# 08-STM32-01.net
KiCad netlist of a schematic drawn in Altium Designer
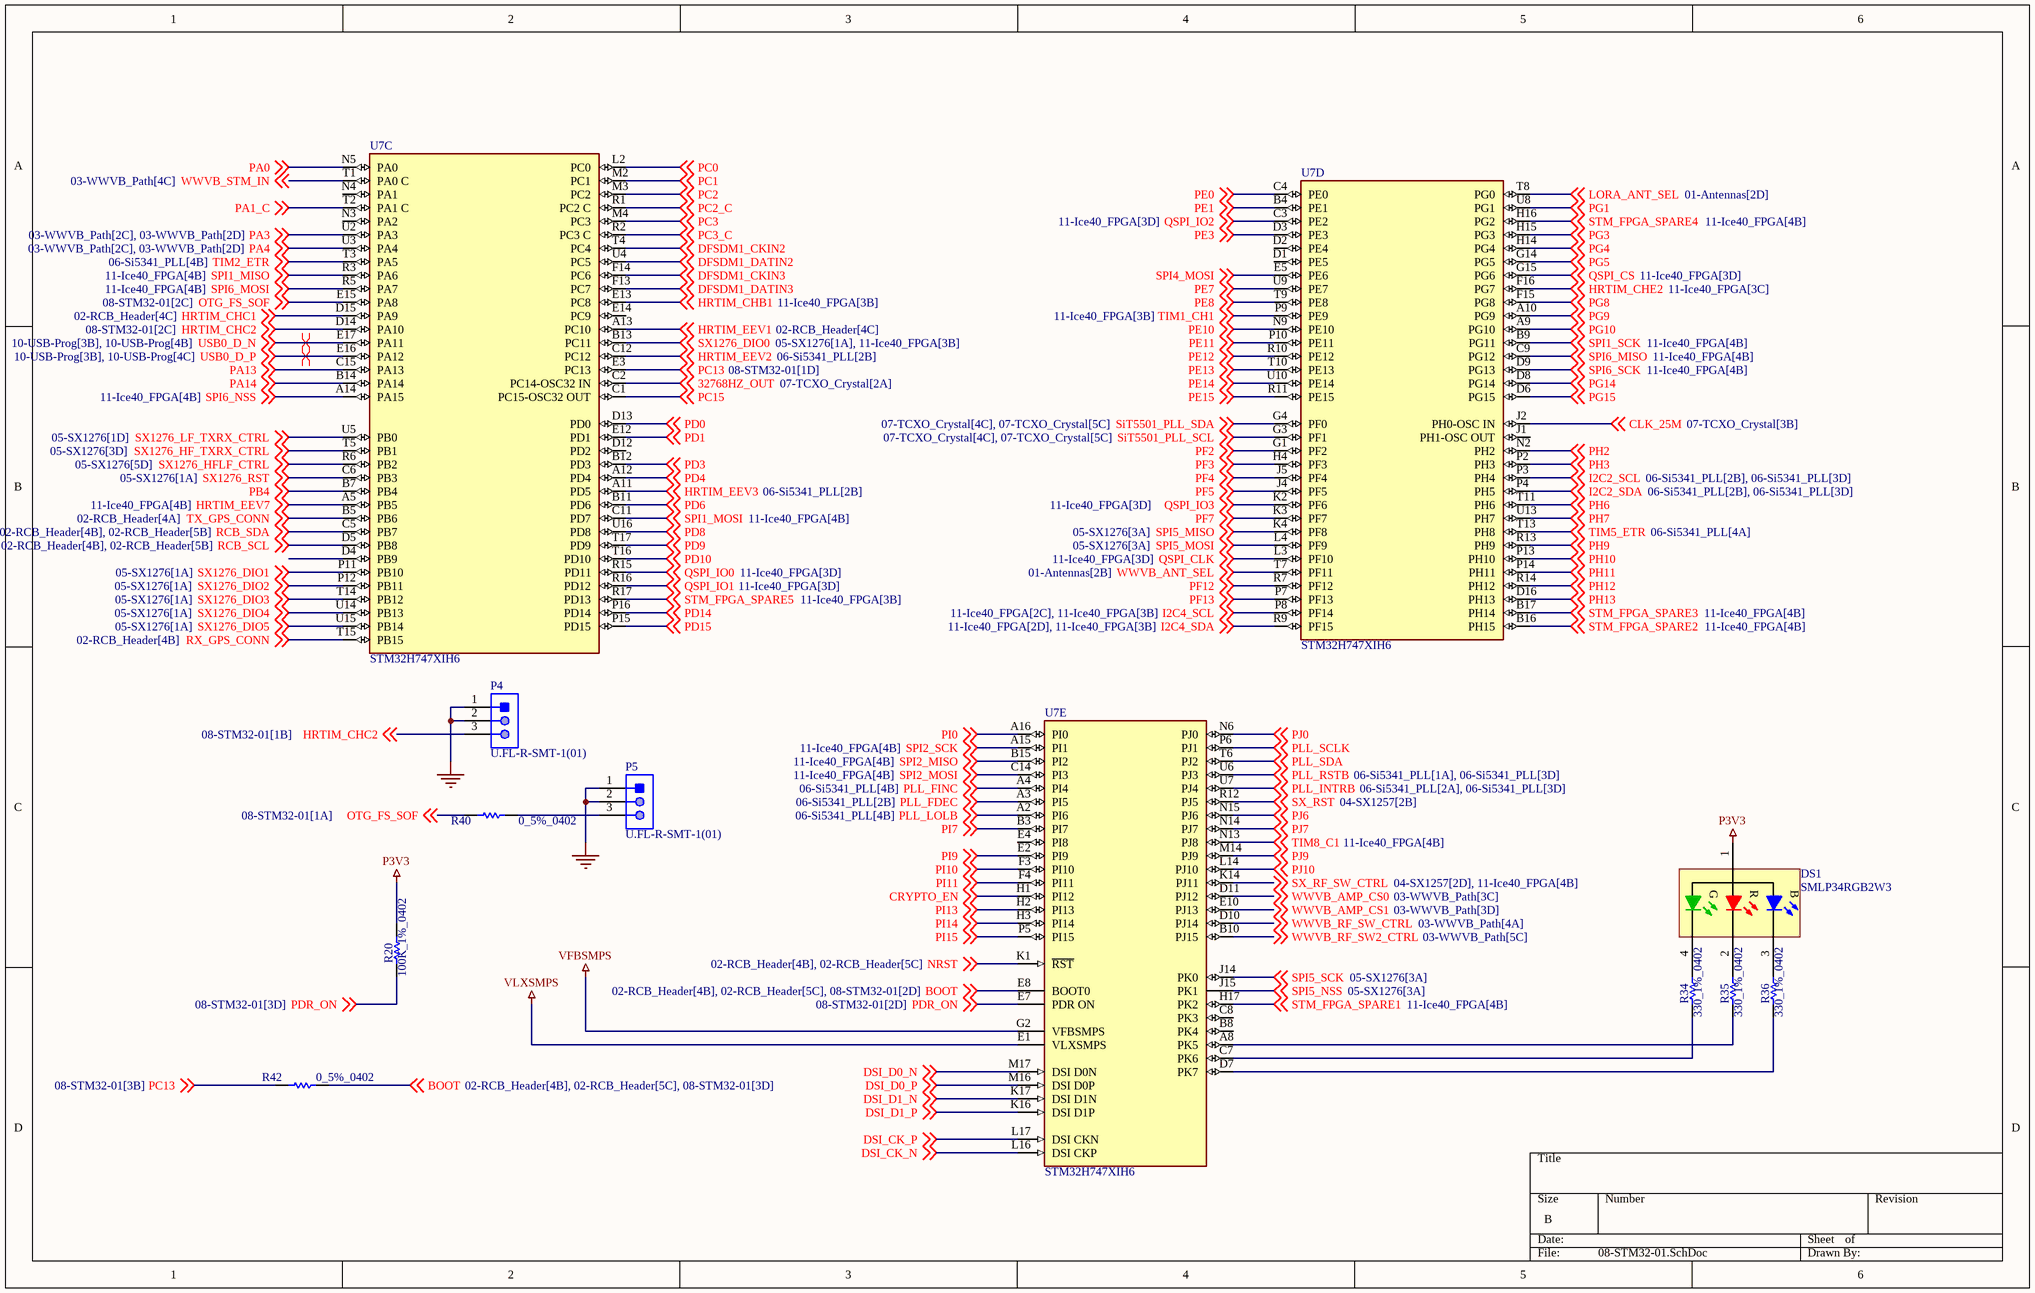
[diagram p0: 08-STM32-01.SchDoc]

(export (version "E")
  (design (tool "Eeschema 10.0.6"))
  (components
    (comp (ref "DS1")
      (value "SMLP34RGB2W3")
      (footprint "ROHM-SMLP34-4_V")
      (description "PICOLED-RGB LED, 5 mA, -40 to 85 degC, 4-Pin 1 x 1 x 0.25 mm SMD, RoHS, Tape and Reel")
      (fields (field (name "MANUFACTURER") "ROHM Semiconductor"))
      (libsource (lib "Altium Content Vault") (part "ROHM-LED_RGB_A1R2B3G4-4"))
    )
    (comp (ref "P4")
      (value "U.FL-R-SMT-1(01)")
      (footprint "HRS-U.FL-R-SMT-3_V")
      (description "Ultra Small Coaxial Connector, 6 GHz, -40 to 90 degC, 3-Pin SMD, RoHS, Bulk")
      (fields (field (name "MANUFACTURER") "Hirose Electric"))
      (libsource (lib "Altium Content Vault") (part "CN-1P-M-R3"))
    )
    (comp (ref "P5")
      (value "U.FL-R-SMT-1(01)")
      (footprint "HRS-U.FL-R-SMT-3_V")
      (description "Ultra Small Coaxial Connector, 6 GHz, -40 to 90 degC, 3-Pin SMD, RoHS, Bulk")
      (fields (field (name "MANUFACTURER") "Hirose Electric"))
      (libsource (lib "Altium Content Vault") (part "CN-1P-M-R3"))
    )
    (comp (ref "R20")
      (value "100K_1%_0402")
      (footprint "RESC1005X40X25ML05T10")
      (fields (field (name "MANUFACTURER") "Yageo") (field (name "PART NUMBER") "RC0402FR-13100KL"))
      (libsource (lib "Altium Content Vault") (part "RES"))
    )
    (comp (ref "R34")
      (value "330_1%_0402")
      (footprint "RESC1005X40X25NL10T10")
      (fields (field (name "MANUFACTURER") "Panasonic") (field (name "PART NUMBER") "ERA-2AED331X"))
      (libsource (lib "Altium Content Vault") (part "RES"))
    )
    (comp (ref "R35")
      (value "330_1%_0402")
      (footprint "RESC1005X40X25NL10T10")
      (fields (field (name "MANUFACTURER") "Panasonic") (field (name "PART NUMBER") "ERA-2AED331X"))
      (libsource (lib "Altium Content Vault") (part "RES"))
    )
    (comp (ref "R36")
      (value "330_1%_0402")
      (footprint "RESC1005X40X25NL10T10")
      (fields (field (name "MANUFACTURER") "Panasonic") (field (name "PART NUMBER") "ERA-2AED331X"))
      (libsource (lib "Altium Content Vault") (part "RES"))
    )
    (comp (ref "R40")
      (value "0_5%_0402")
      (footprint "RESC1005X40X25NL05T10")
      (fields (field (name "MANUFACTURER") "Panasonic") (field (name "PART NUMBER") "ERJ-U020R00X"))
      (libsource (lib "Altium Content Vault") (part "RES"))
    )
    (comp (ref "R42")
      (value "0_5%_0402")
      (footprint "RESC1005X40X25NL05T10")
      (fields (field (name "MANUFACTURER") "Panasonic") (field (name "PART NUMBER") "ERJ-U020R00X"))
      (libsource (lib "Altium Content Vault") (part "RES"))
    )
    (comp (ref "U7")
      (value "STM32H747XIH6")
      (footprint "FP-TFBGA240+25-A07U-MFG")
      (description "HIGH-PERFORMANCE AND DSP WITH DP")
      (fields
        (field (name "MANUFACTURER") "STMicroelectronics")
        (field (name "OCTOPART") "https://octopart.com/stm32h747xih6-stmicroelectronics-100293943")
      )
      (libsource (lib "Altium Content Vault") (part "41f839bdfd00d9510c8672f0f410bfb"))
    )
  )
  (nets
    (net (code "1") (name "32768HZ_OUT") (class "Default")
      (node (ref "U7") (pin "C2") (pinfunction "PC14-OSC32_IN_C2") (pintype "bidirectional"))
    )
    (net (code "2") (name "BOOT") (class "Default")
      (node (ref "R42") (pin "2") (pinfunction "2_2") (pintype "passive"))
      (node (ref "U7") (pin "E8") (pinfunction "BOOT0_E8") (pintype "passive"))
    )
    (net (code "3") (name "CLK_25M") (class "Default")
      (node (ref "U7") (pin "J2") (pinfunction "PH0-OSC_IN_J2") (pintype "bidirectional"))
    )
    (net (code "4") (name "CRYPTO_EN") (class "Default")
      (node (ref "U7") (pin "H1") (pinfunction "PI12_H1") (pintype "bidirectional"))
    )
    (net (code "5") (name "DFSDM1_CKIN2") (class "Default")
      (node (ref "U7") (pin "T4") (pinfunction "PC4_T4") (pintype "bidirectional"))
    )
    (net (code "6") (name "DFSDM1_CKIN3") (class "Default")
      (node (ref "U7") (pin "F14") (pinfunction "PC6_F14") (pintype "bidirectional"))
    )
    (net (code "7") (name "DFSDM1_DATIN2") (class "Default")
      (node (ref "U7") (pin "U4") (pinfunction "PC5_U4") (pintype "bidirectional"))
    )
    (net (code "8") (name "DFSDM1_DATIN3") (class "Default")
      (node (ref "U7") (pin "F13") (pinfunction "PC7_F13") (pintype "bidirectional"))
    )
    (net (code "9") (name "DSI_CK_N") (class "Default")
      (node (ref "U7") (pin "L16") (pinfunction "DSI_CKP_L16") (pintype "input"))
    )
    (net (code "10") (name "DSI_CK_P") (class "Default")
      (node (ref "U7") (pin "L17") (pinfunction "DSI_CKN_L17") (pintype "input"))
    )
    (net (code "11") (name "DSI_D0_N") (class "Default")
      (node (ref "U7") (pin "M17") (pinfunction "DSI_D0N_M17") (pintype "input"))
    )
    (net (code "12") (name "DSI_D0_P") (class "Default")
      (node (ref "U7") (pin "M16") (pinfunction "DSI_D0P_M16") (pintype "input"))
    )
    (net (code "13") (name "DSI_D1_N") (class "Default")
      (node (ref "U7") (pin "K17") (pinfunction "DSI_D1N_K17") (pintype "input"))
    )
    (net (code "14") (name "DSI_D1_P") (class "Default")
      (node (ref "U7") (pin "K16") (pinfunction "DSI_D1P_K16") (pintype "input"))
    )
    (net (code "15") (name "GND") (class "Default")
      (node (ref "P4") (pin "1") (pinfunction "1_1") (pintype "passive"))
      (node (ref "P4") (pin "2") (pinfunction "2_2") (pintype "passive"))
      (node (ref "P5") (pin "1") (pinfunction "1_1") (pintype "passive"))
      (node (ref "P5") (pin "2") (pinfunction "2_2") (pintype "passive"))
    )
    (net (code "16") (name "HRTIM_CHB1") (class "Default")
      (node (ref "U7") (pin "E13") (pinfunction "PC8_E13") (pintype "bidirectional"))
    )
    (net (code "17") (name "HRTIM_CHC1") (class "Default")
      (node (ref "U7") (pin "D15") (pinfunction "PA9_D15") (pintype "bidirectional"))
    )
    (net (code "18") (name "HRTIM_CHC2") (class "Default")
      (node (ref "P4") (pin "3") (pinfunction "3_3") (pintype "passive"))
      (node (ref "U7") (pin "D14") (pinfunction "PA10_D14") (pintype "bidirectional"))
    )
    (net (code "19") (name "HRTIM_CHE2") (class "Default")
      (node (ref "U7") (pin "F16") (pinfunction "PG7_F16") (pintype "bidirectional"))
    )
    (net (code "20") (name "HRTIM_EEV1") (class "Default")
      (node (ref "U7") (pin "A13") (pinfunction "PC10_A13") (pintype "bidirectional"))
    )
    (net (code "21") (name "HRTIM_EEV2") (class "Default")
      (node (ref "U7") (pin "C12") (pinfunction "PC12_C12") (pintype "bidirectional"))
    )
    (net (code "22") (name "HRTIM_EEV3") (class "Default")
      (node (ref "U7") (pin "A11") (pinfunction "PD5_A11") (pintype "bidirectional"))
    )
    (net (code "23") (name "HRTIM_EEV7") (class "Default")
      (node (ref "U7") (pin "A5") (pinfunction "PB5_A5") (pintype "bidirectional"))
    )
    (net (code "24") (name "I2C2_SCL") (class "Default")
      (node (ref "U7") (pin "P3") (pinfunction "PH4_P3") (pintype "bidirectional"))
    )
    (net (code "25") (name "I2C2_SDA") (class "Default")
      (node (ref "U7") (pin "P4") (pinfunction "PH5_P4") (pintype "bidirectional"))
    )
    (net (code "26") (name "I2C4_SCL") (class "Default")
      (node (ref "U7") (pin "P8") (pinfunction "PF14_P8") (pintype "bidirectional"))
    )
    (net (code "27") (name "I2C4_SDA") (class "Default")
      (node (ref "U7") (pin "R9") (pinfunction "PF15_R9") (pintype "bidirectional"))
    )
    (net (code "28") (name "LORA_ANT_SEL") (class "Default")
      (node (ref "U7") (pin "T8") (pinfunction "PG0_T8") (pintype "bidirectional"))
    )
    (net (code "29") (name "NRST") (class "Default")
      (node (ref "U7") (pin "K1") (pinfunction "~{RST}_K1") (pintype "input"))
    )
    (net (code "30") (name "Net-(DS1-B)") (class "Default")
      (node (ref "DS1") (pin "3") (pinfunction "B_3") (pintype "passive"))
      (node (ref "R36") (pin "2") (pinfunction "2_2") (pintype "passive"))
    )
    (net (code "31") (name "Net-(DS1-G)") (class "Default")
      (node (ref "DS1") (pin "4") (pinfunction "G_4") (pintype "passive"))
      (node (ref "R34") (pin "2") (pinfunction "2_2") (pintype "passive"))
    )
    (net (code "32") (name "Net-(DS1-R)") (class "Default")
      (node (ref "DS1") (pin "2") (pinfunction "R_2") (pintype "passive"))
      (node (ref "R35") (pin "2") (pinfunction "2_2") (pintype "passive"))
    )
    (net (code "33") (name "Net-(P5-Pad3)") (class "Default")
      (node (ref "P5") (pin "3") (pinfunction "3_3") (pintype "passive"))
      (node (ref "R40") (pin "2") (pinfunction "2_2") (pintype "passive"))
    )
    (net (code "34") (name "Net-(U7E-PK5)") (class "Default")
      (node (ref "R35") (pin "1") (pinfunction "1_1") (pintype "passive"))
      (node (ref "U7") (pin "A8") (pinfunction "PK5_A8") (pintype "bidirectional"))
    )
    (net (code "35") (name "Net-(U7E-PK6)") (class "Default")
      (node (ref "R34") (pin "1") (pinfunction "1_1") (pintype "passive"))
      (node (ref "U7") (pin "C7") (pinfunction "PK6_C7") (pintype "bidirectional"))
    )
    (net (code "36") (name "Net-(U7E-PK7)") (class "Default")
      (node (ref "R36") (pin "1") (pinfunction "1_1") (pintype "passive"))
      (node (ref "U7") (pin "D7") (pinfunction "PK7_D7") (pintype "bidirectional"))
    )
    (net (code "37") (name "OTG_FS_SOF") (class "Default")
      (node (ref "R40") (pin "1") (pinfunction "1_1") (pintype "passive"))
      (node (ref "U7") (pin "E15") (pinfunction "PA8_E15") (pintype "bidirectional"))
    )
    (net (code "38") (name "P3V3") (class "Default")
      (node (ref "DS1") (pin "1") (pinfunction "A_1") (pintype "passive"))
      (node (ref "R20") (pin "2") (pinfunction "2_2") (pintype "passive"))
    )
    (net (code "39") (name "PA0") (class "Default")
      (node (ref "U7") (pin "N5") (pinfunction "PA0_N5") (pintype "bidirectional"))
    )
    (net (code "40") (name "PA1_C") (class "Default")
      (node (ref "U7") (pin "T2") (pinfunction "PA1_C_T2") (pintype "bidirectional"))
    )
    (net (code "41") (name "PA3") (class "Default")
      (node (ref "U7") (pin "U2") (pinfunction "PA3_U2") (pintype "bidirectional"))
    )
    (net (code "42") (name "PA4") (class "Default")
      (node (ref "U7") (pin "U3") (pinfunction "PA4_U3") (pintype "bidirectional"))
    )
    (net (code "43") (name "PA13") (class "Default")
      (node (ref "U7") (pin "C15") (pinfunction "PA13_C15") (pintype "bidirectional"))
    )
    (net (code "44") (name "PA14") (class "Default")
      (node (ref "U7") (pin "B14") (pinfunction "PA14_B14") (pintype "bidirectional"))
    )
    (net (code "45") (name "PB4") (class "Default")
      (node (ref "U7") (pin "B7") (pinfunction "PB4_B7") (pintype "bidirectional"))
    )
    (net (code "46") (name "PC0") (class "Default")
      (node (ref "U7") (pin "L2") (pinfunction "PC0_L2") (pintype "bidirectional"))
    )
    (net (code "47") (name "PC1") (class "Default")
      (node (ref "U7") (pin "M2") (pinfunction "PC1_M2") (pintype "bidirectional"))
    )
    (net (code "48") (name "PC2") (class "Default")
      (node (ref "U7") (pin "M3") (pinfunction "PC2_M3") (pintype "bidirectional"))
    )
    (net (code "49") (name "PC2_C") (class "Default")
      (node (ref "U7") (pin "R1") (pinfunction "PC2_C_R1") (pintype "bidirectional"))
    )
    (net (code "50") (name "PC3") (class "Default")
      (node (ref "U7") (pin "M4") (pinfunction "PC3_M4") (pintype "bidirectional"))
    )
    (net (code "51") (name "PC3_C") (class "Default")
      (node (ref "U7") (pin "R2") (pinfunction "PC3_C_R2") (pintype "bidirectional"))
    )
    (net (code "52") (name "PC13") (class "Default")
      (node (ref "R42") (pin "1") (pinfunction "1_1") (pintype "passive"))
      (node (ref "U7") (pin "E3") (pinfunction "PC13_E3") (pintype "bidirectional"))
    )
    (net (code "53") (name "PC15") (class "Default")
      (node (ref "U7") (pin "C1") (pinfunction "PC15-OSC32_OUT_C1") (pintype "bidirectional"))
    )
    (net (code "54") (name "PD0") (class "Default")
      (node (ref "U7") (pin "D13") (pinfunction "PD0_D13") (pintype "bidirectional"))
    )
    (net (code "55") (name "PD1") (class "Default")
      (node (ref "U7") (pin "E12") (pinfunction "PD1_E12") (pintype "bidirectional"))
    )
    (net (code "56") (name "PD3") (class "Default")
      (node (ref "U7") (pin "B12") (pinfunction "PD3_B12") (pintype "bidirectional"))
    )
    (net (code "57") (name "PD4") (class "Default")
      (node (ref "U7") (pin "A12") (pinfunction "PD4_A12") (pintype "bidirectional"))
    )
    (net (code "58") (name "PD6") (class "Default")
      (node (ref "U7") (pin "B11") (pinfunction "PD6_B11") (pintype "bidirectional"))
    )
    (net (code "59") (name "PD8") (class "Default")
      (node (ref "U7") (pin "U16") (pinfunction "PD8_U16") (pintype "bidirectional"))
    )
    (net (code "60") (name "PD9") (class "Default")
      (node (ref "U7") (pin "T17") (pinfunction "PD9_T17") (pintype "bidirectional"))
    )
    (net (code "61") (name "PD10") (class "Default")
      (node (ref "U7") (pin "T16") (pinfunction "PD10_T16") (pintype "bidirectional"))
    )
    (net (code "62") (name "PD14") (class "Default")
      (node (ref "U7") (pin "P16") (pinfunction "PD14_P16") (pintype "bidirectional"))
    )
    (net (code "63") (name "PD15") (class "Default")
      (node (ref "U7") (pin "P15") (pinfunction "PD15_P15") (pintype "bidirectional"))
    )
    (net (code "64") (name "PDR_ON") (class "Default")
      (node (ref "R20") (pin "1") (pinfunction "1_1") (pintype "passive"))
      (node (ref "U7") (pin "E7") (pinfunction "PDR_ON_E7") (pintype "power_in"))
    )
    (net (code "65") (name "PE0") (class "Default")
      (node (ref "U7") (pin "C4") (pinfunction "PE0_C4") (pintype "bidirectional"))
    )
    (net (code "66") (name "PE1") (class "Default")
      (node (ref "U7") (pin "B4") (pinfunction "PE1_B4") (pintype "bidirectional"))
    )
    (net (code "67") (name "PE3") (class "Default")
      (node (ref "U7") (pin "D3") (pinfunction "PE3_D3") (pintype "bidirectional"))
    )
    (net (code "68") (name "PE7") (class "Default")
      (node (ref "U7") (pin "U9") (pinfunction "PE7_U9") (pintype "bidirectional"))
    )
    (net (code "69") (name "PE8") (class "Default")
      (node (ref "U7") (pin "T9") (pinfunction "PE8_T9") (pintype "bidirectional"))
    )
    (net (code "70") (name "PE10") (class "Default")
      (node (ref "U7") (pin "N9") (pinfunction "PE10_N9") (pintype "bidirectional"))
    )
    (net (code "71") (name "PE11") (class "Default")
      (node (ref "U7") (pin "P10") (pinfunction "PE11_P10") (pintype "bidirectional"))
    )
    (net (code "72") (name "PE12") (class "Default")
      (node (ref "U7") (pin "R10") (pinfunction "PE12_R10") (pintype "bidirectional"))
    )
    (net (code "73") (name "PE13") (class "Default")
      (node (ref "U7") (pin "T10") (pinfunction "PE13_T10") (pintype "bidirectional"))
    )
    (net (code "74") (name "PE14") (class "Default")
      (node (ref "U7") (pin "U10") (pinfunction "PE14_U10") (pintype "bidirectional"))
    )
    (net (code "75") (name "PE15") (class "Default")
      (node (ref "U7") (pin "R11") (pinfunction "PE15_R11") (pintype "bidirectional"))
    )
    (net (code "76") (name "PF2") (class "Default")
      (node (ref "U7") (pin "G1") (pinfunction "PF2_G1") (pintype "bidirectional"))
    )
    (net (code "77") (name "PF3") (class "Default")
      (node (ref "U7") (pin "H4") (pinfunction "PF3_H4") (pintype "bidirectional"))
    )
    (net (code "78") (name "PF4") (class "Default")
      (node (ref "U7") (pin "J5") (pinfunction "PF4_J5") (pintype "bidirectional"))
    )
    (net (code "79") (name "PF5") (class "Default")
      (node (ref "U7") (pin "J4") (pinfunction "PF5_J4") (pintype "bidirectional"))
    )
    (net (code "80") (name "PF7") (class "Default")
      (node (ref "U7") (pin "K3") (pinfunction "PF7_K3") (pintype "bidirectional"))
    )
    (net (code "81") (name "PF12") (class "Default")
      (node (ref "U7") (pin "R7") (pinfunction "PF12_R7") (pintype "bidirectional"))
    )
    (net (code "82") (name "PF13") (class "Default")
      (node (ref "U7") (pin "P7") (pinfunction "PF13_P7") (pintype "bidirectional"))
    )
    (net (code "83") (name "PG1") (class "Default")
      (node (ref "U7") (pin "U8") (pinfunction "PG1_U8") (pintype "bidirectional"))
    )
    (net (code "84") (name "PG3") (class "Default")
      (node (ref "U7") (pin "H15") (pinfunction "PG3_H15") (pintype "bidirectional"))
    )
    (net (code "85") (name "PG4") (class "Default")
      (node (ref "U7") (pin "H14") (pinfunction "PG4_H14") (pintype "bidirectional"))
    )
    (net (code "86") (name "PG5") (class "Default")
      (node (ref "U7") (pin "G14") (pinfunction "PG5_G14") (pintype "bidirectional"))
    )
    (net (code "87") (name "PG8") (class "Default")
      (node (ref "U7") (pin "F15") (pinfunction "PG8_F15") (pintype "bidirectional"))
    )
    (net (code "88") (name "PG9") (class "Default")
      (node (ref "U7") (pin "A10") (pinfunction "PG9_A10") (pintype "bidirectional"))
    )
    (net (code "89") (name "PG10") (class "Default")
      (node (ref "U7") (pin "A9") (pinfunction "PG10_A9") (pintype "bidirectional"))
    )
    (net (code "90") (name "PG14") (class "Default")
      (node (ref "U7") (pin "D8") (pinfunction "PG14_D8") (pintype "bidirectional"))
    )
    (net (code "91") (name "PG15") (class "Default")
      (node (ref "U7") (pin "D6") (pinfunction "PG15_D6") (pintype "bidirectional"))
    )
    (net (code "92") (name "PH2") (class "Default")
      (node (ref "U7") (pin "N2") (pinfunction "PH2_N2") (pintype "bidirectional"))
    )
    (net (code "93") (name "PH3") (class "Default")
      (node (ref "U7") (pin "P2") (pinfunction "PH3_P2") (pintype "bidirectional"))
    )
    (net (code "94") (name "PH6") (class "Default")
      (node (ref "U7") (pin "T11") (pinfunction "PH6_T11") (pintype "bidirectional"))
    )
    (net (code "95") (name "PH7") (class "Default")
      (node (ref "U7") (pin "U13") (pinfunction "PH7_U13") (pintype "bidirectional"))
    )
    (net (code "96") (name "PH9") (class "Default")
      (node (ref "U7") (pin "R13") (pinfunction "PH9_R13") (pintype "bidirectional"))
    )
    (net (code "97") (name "PH10") (class "Default")
      (node (ref "U7") (pin "P13") (pinfunction "PH10_P13") (pintype "bidirectional"))
    )
    (net (code "98") (name "PH11") (class "Default")
      (node (ref "U7") (pin "P14") (pinfunction "PH11_P14") (pintype "bidirectional"))
    )
    (net (code "99") (name "PH12") (class "Default")
      (node (ref "U7") (pin "R14") (pinfunction "PH12_R14") (pintype "bidirectional"))
    )
    (net (code "100") (name "PH13") (class "Default")
      (node (ref "U7") (pin "D16") (pinfunction "PH13_D16") (pintype "bidirectional"))
    )
    (net (code "101") (name "PI0") (class "Default")
      (node (ref "U7") (pin "A16") (pinfunction "PI0_A16") (pintype "bidirectional"))
    )
    (net (code "102") (name "PI7") (class "Default")
      (node (ref "U7") (pin "B3") (pinfunction "PI7_B3") (pintype "bidirectional"))
    )
    (net (code "103") (name "PI9") (class "Default")
      (node (ref "U7") (pin "E2") (pinfunction "PI9_E2") (pintype "bidirectional"))
    )
    (net (code "104") (name "PI10") (class "Default")
      (node (ref "U7") (pin "F3") (pinfunction "PI10_F3") (pintype "bidirectional"))
    )
    (net (code "105") (name "PI11") (class "Default")
      (node (ref "U7") (pin "F4") (pinfunction "PI11_F4") (pintype "bidirectional"))
    )
    (net (code "106") (name "PI13") (class "Default")
      (node (ref "U7") (pin "H2") (pinfunction "PI13_H2") (pintype "bidirectional"))
    )
    (net (code "107") (name "PI14") (class "Default")
      (node (ref "U7") (pin "H3") (pinfunction "PI14_H3") (pintype "bidirectional"))
    )
    (net (code "108") (name "PI15") (class "Default")
      (node (ref "U7") (pin "P5") (pinfunction "PI15_P5") (pintype "bidirectional"))
    )
    (net (code "109") (name "PJ0") (class "Default")
      (node (ref "U7") (pin "N6") (pinfunction "PJ0_N6") (pintype "bidirectional"))
    )
    (net (code "110") (name "PJ6") (class "Default")
      (node (ref "U7") (pin "N15") (pinfunction "PJ6_N15") (pintype "bidirectional"))
    )
    (net (code "111") (name "PJ7") (class "Default")
      (node (ref "U7") (pin "N14") (pinfunction "PJ7_N14") (pintype "bidirectional"))
    )
    (net (code "112") (name "PJ9") (class "Default")
      (node (ref "U7") (pin "M14") (pinfunction "PJ9_M14") (pintype "bidirectional"))
    )
    (net (code "113") (name "PJ10") (class "Default")
      (node (ref "U7") (pin "L14") (pinfunction "PJ10_L14") (pintype "bidirectional"))
    )
    (net (code "114") (name "PLL_FDEC") (class "Default")
      (node (ref "U7") (pin "A3") (pinfunction "PI5_A3") (pintype "bidirectional"))
    )
    (net (code "115") (name "PLL_FINC") (class "Default")
      (node (ref "U7") (pin "A4") (pinfunction "PI4_A4") (pintype "bidirectional"))
    )
    (net (code "116") (name "PLL_INTRB") (class "Default")
      (node (ref "U7") (pin "U7") (pinfunction "PJ4_U7") (pintype "bidirectional"))
    )
    (net (code "117") (name "PLL_LOLB") (class "Default")
      (node (ref "U7") (pin "A2") (pinfunction "PI6_A2") (pintype "bidirectional"))
    )
    (net (code "118") (name "PLL_RSTB") (class "Default")
      (node (ref "U7") (pin "U6") (pinfunction "PJ3_U6") (pintype "bidirectional"))
    )
    (net (code "119") (name "PLL_SCLK") (class "Default")
      (node (ref "U7") (pin "P6") (pinfunction "PJ1_P6") (pintype "bidirectional"))
    )
    (net (code "120") (name "PLL_SDA") (class "Default")
      (node (ref "U7") (pin "T6") (pinfunction "PJ2_T6") (pintype "bidirectional"))
    )
    (net (code "121") (name "QSPI_CLK") (class "Default")
      (node (ref "U7") (pin "L3") (pinfunction "PF10_L3") (pintype "bidirectional"))
    )
    (net (code "122") (name "QSPI_CS") (class "Default")
      (node (ref "U7") (pin "G15") (pinfunction "PG6_G15") (pintype "bidirectional"))
    )
    (net (code "123") (name "QSPI_IO0") (class "Default")
      (node (ref "U7") (pin "R15") (pinfunction "PD11_R15") (pintype "bidirectional"))
    )
    (net (code "124") (name "QSPI_IO1") (class "Default")
      (node (ref "U7") (pin "R16") (pinfunction "PD12_R16") (pintype "bidirectional"))
    )
    (net (code "125") (name "QSPI_IO2") (class "Default")
      (node (ref "U7") (pin "C3") (pinfunction "PE2_C3") (pintype "bidirectional"))
    )
    (net (code "126") (name "QSPI_IO3") (class "Default")
      (node (ref "U7") (pin "K2") (pinfunction "PF6_K2") (pintype "bidirectional"))
    )
    (net (code "127") (name "RCB_SCL") (class "Default")
      (node (ref "U7") (pin "D5") (pinfunction "PB8_D5") (pintype "bidirectional"))
    )
    (net (code "128") (name "RCB_SDA") (class "Default")
      (node (ref "U7") (pin "C5") (pinfunction "PB7_C5") (pintype "bidirectional"))
    )
    (net (code "129") (name "RX_GPS_CONN") (class "Default")
      (node (ref "U7") (pin "T15") (pinfunction "PB15_T15") (pintype "bidirectional"))
    )
    (net (code "130") (name "SPI1_MISO") (class "Default")
      (node (ref "U7") (pin "R3") (pinfunction "PA6_R3") (pintype "bidirectional"))
    )
    (net (code "131") (name "SPI1_MOSI") (class "Default")
      (node (ref "U7") (pin "C11") (pinfunction "PD7_C11") (pintype "bidirectional"))
    )
    (net (code "132") (name "SPI1_SCK") (class "Default")
      (node (ref "U7") (pin "B9") (pinfunction "PG11_B9") (pintype "bidirectional"))
    )
    (net (code "133") (name "SPI2_MISO") (class "Default")
      (node (ref "U7") (pin "B15") (pinfunction "PI2_B15") (pintype "bidirectional"))
    )
    (net (code "134") (name "SPI2_MOSI") (class "Default")
      (node (ref "U7") (pin "C14") (pinfunction "PI3_C14") (pintype "bidirectional"))
    )
    (net (code "135") (name "SPI2_SCK") (class "Default")
      (node (ref "U7") (pin "A15") (pinfunction "PI1_A15") (pintype "bidirectional"))
    )
    (net (code "136") (name "SPI4_MOSI") (class "Default")
      (node (ref "U7") (pin "E5") (pinfunction "PE6_E5") (pintype "bidirectional"))
    )
    (net (code "137") (name "SPI5_MISO") (class "Default")
      (node (ref "U7") (pin "K4") (pinfunction "PF8_K4") (pintype "bidirectional"))
    )
    (net (code "138") (name "SPI5_MOSI") (class "Default")
      (node (ref "U7") (pin "L4") (pinfunction "PF9_L4") (pintype "bidirectional"))
    )
    (net (code "139") (name "SPI5_NSS") (class "Default")
      (node (ref "U7") (pin "J15") (pinfunction "PK1_J15") (pintype "passive"))
    )
    (net (code "140") (name "SPI5_SCK") (class "Default")
      (node (ref "U7") (pin "J14") (pinfunction "PK0_J14") (pintype "bidirectional"))
    )
    (net (code "141") (name "SPI6_MISO") (class "Default")
      (node (ref "U7") (pin "C9") (pinfunction "PG12_C9") (pintype "bidirectional"))
    )
    (net (code "142") (name "SPI6_MOSI") (class "Default")
      (node (ref "U7") (pin "R5") (pinfunction "PA7_R5") (pintype "bidirectional"))
    )
    (net (code "143") (name "SPI6_NSS") (class "Default")
      (node (ref "U7") (pin "A14") (pinfunction "PA15_A14") (pintype "bidirectional"))
    )
    (net (code "144") (name "SPI6_SCK") (class "Default")
      (node (ref "U7") (pin "D9") (pinfunction "PG13_D9") (pintype "bidirectional"))
    )
    (net (code "145") (name "STM_FPGA_SPARE1") (class "Default")
      (node (ref "U7") (pin "H17") (pinfunction "PK2_H17") (pintype "bidirectional"))
    )
    (net (code "146") (name "STM_FPGA_SPARE2") (class "Default")
      (node (ref "U7") (pin "B16") (pinfunction "PH15_B16") (pintype "bidirectional"))
    )
    (net (code "147") (name "STM_FPGA_SPARE3") (class "Default")
      (node (ref "U7") (pin "B17") (pinfunction "PH14_B17") (pintype "bidirectional"))
    )
    (net (code "148") (name "STM_FPGA_SPARE4") (class "Default")
      (node (ref "U7") (pin "H16") (pinfunction "PG2_H16") (pintype "bidirectional"))
    )
    (net (code "149") (name "STM_FPGA_SPARE5") (class "Default")
      (node (ref "U7") (pin "R17") (pinfunction "PD13_R17") (pintype "bidirectional"))
    )
    (net (code "150") (name "SX1276_DIO0") (class "Default")
      (node (ref "U7") (pin "B13") (pinfunction "PC11_B13") (pintype "bidirectional"))
    )
    (net (code "151") (name "SX1276_DIO1") (class "Default")
      (node (ref "U7") (pin "P11") (pinfunction "PB10_P11") (pintype "bidirectional"))
    )
    (net (code "152") (name "SX1276_DIO2") (class "Default")
      (node (ref "U7") (pin "P12") (pinfunction "PB11_P12") (pintype "bidirectional"))
    )
    (net (code "153") (name "SX1276_DIO3") (class "Default")
      (node (ref "U7") (pin "T14") (pinfunction "PB12_T14") (pintype "bidirectional"))
    )
    (net (code "154") (name "SX1276_DIO4") (class "Default")
      (node (ref "U7") (pin "U14") (pinfunction "PB13_U14") (pintype "bidirectional"))
    )
    (net (code "155") (name "SX1276_DIO5") (class "Default")
      (node (ref "U7") (pin "U15") (pinfunction "PB14_U15") (pintype "bidirectional"))
    )
    (net (code "156") (name "SX1276_HFLF_CTRL") (class "Default")
      (node (ref "U7") (pin "R6") (pinfunction "PB2_R6") (pintype "bidirectional"))
    )
    (net (code "157") (name "SX1276_HF_TXRX_CTRL") (class "Default")
      (node (ref "U7") (pin "T5") (pinfunction "PB1_T5") (pintype "bidirectional"))
    )
    (net (code "158") (name "SX1276_LF_TXRX_CTRL") (class "Default")
      (node (ref "U7") (pin "U5") (pinfunction "PB0_U5") (pintype "bidirectional"))
    )
    (net (code "159") (name "SX1276_RST") (class "Default")
      (node (ref "U7") (pin "C6") (pinfunction "PB3_C6") (pintype "bidirectional"))
    )
    (net (code "160") (name "SX_RF_SW_CTRL") (class "Default")
      (node (ref "U7") (pin "K14") (pinfunction "PJ11_K14") (pintype "bidirectional"))
    )
    (net (code "161") (name "SX_RST") (class "Default")
      (node (ref "U7") (pin "R12") (pinfunction "PJ5_R12") (pintype "bidirectional"))
    )
    (net (code "162") (name "SiT5501_PLL_SCL") (class "Default")
      (node (ref "U7") (pin "G3") (pinfunction "PF1_G3") (pintype "bidirectional"))
    )
    (net (code "163") (name "SiT5501_PLL_SDA") (class "Default")
      (node (ref "U7") (pin "G4") (pinfunction "PF0_G4") (pintype "bidirectional"))
    )
    (net (code "164") (name "TIM1_CH1") (class "Default")
      (node (ref "U7") (pin "P9") (pinfunction "PE9_P9") (pintype "bidirectional"))
    )
    (net (code "165") (name "TIM2_ETR") (class "Default")
      (node (ref "U7") (pin "T3") (pinfunction "PA5_T3") (pintype "bidirectional"))
    )
    (net (code "166") (name "TIM5_ETR") (class "Default")
      (node (ref "U7") (pin "T13") (pinfunction "PH8_T13") (pintype "bidirectional"))
    )
    (net (code "167") (name "TIM8_C1") (class "Default")
      (node (ref "U7") (pin "N13") (pinfunction "PJ8_N13") (pintype "bidirectional"))
    )
    (net (code "168") (name "TX_GPS_CONN") (class "Default")
      (node (ref "U7") (pin "B5") (pinfunction "PB6_B5") (pintype "bidirectional"))
    )
    (net (code "169") (name "USB0_D_N") (class "Default")
      (node (ref "U7") (pin "E17") (pinfunction "PA11_E17") (pintype "bidirectional"))
    )
    (net (code "170") (name "USB0_D_P") (class "Default")
      (node (ref "U7") (pin "E16") (pinfunction "PA12_E16") (pintype "bidirectional"))
    )
    (net (code "171") (name "VFBSMPS") (class "Default")
      (node (ref "U7") (pin "G2") (pinfunction "VFBSMPS_G2") (pintype "power_in"))
    )
    (net (code "172") (name "VLXSMPS") (class "Default")
      (node (ref "U7") (pin "E1") (pinfunction "VLXSMPS_E1") (pintype "power_in"))
    )
    (net (code "173") (name "WWVB_AMP_CS0") (class "Default")
      (node (ref "U7") (pin "D11") (pinfunction "PJ12_D11") (pintype "bidirectional"))
    )
    (net (code "174") (name "WWVB_AMP_CS1") (class "Default")
      (node (ref "U7") (pin "E10") (pinfunction "PJ13_E10") (pintype "bidirectional"))
    )
    (net (code "175") (name "WWVB_ANT_SEL") (class "Default")
      (node (ref "U7") (pin "T7") (pinfunction "PF11_T7") (pintype "bidirectional"))
    )
    (net (code "176") (name "WWVB_RF_SW2_CTRL") (class "Default")
      (node (ref "U7") (pin "B10") (pinfunction "PJ15_B10") (pintype "bidirectional"))
    )
    (net (code "177") (name "WWVB_RF_SW_CTRL") (class "Default")
      (node (ref "U7") (pin "D10") (pinfunction "PJ14_D10") (pintype "bidirectional"))
    )
    (net (code "178") (name "WWVB_STM_IN") (class "Default")
      (node (ref "U7") (pin "T1") (pinfunction "PA0_C_T1") (pintype "bidirectional"))
    )
    (net (code "179") (name "unconnected-(U7C-PA1-PadN4)") (class "Default")
      (node (ref "U7") (pin "N4") (pinfunction "PA1_N4") (pintype "bidirectional"))
    )
    (net (code "180") (name "unconnected-(U7C-PA2-PadN3)") (class "Default")
      (node (ref "U7") (pin "N3") (pinfunction "PA2_N3") (pintype "bidirectional"))
    )
    (net (code "181") (name "unconnected-(U7C-PB9-PadD4)") (class "Default")
      (node (ref "U7") (pin "D4") (pinfunction "PB9_D4") (pintype "bidirectional"))
    )
    (net (code "182") (name "unconnected-(U7C-PC9-PadE14)") (class "Default")
      (node (ref "U7") (pin "E14") (pinfunction "PC9_E14") (pintype "bidirectional"))
    )
    (net (code "183") (name "unconnected-(U7C-PD2-PadD12)") (class "Default")
      (node (ref "U7") (pin "D12") (pinfunction "PD2_D12") (pintype "bidirectional"))
    )
    (net (code "184") (name "unconnected-(U7D-PE4-PadD2)") (class "Default")
      (node (ref "U7") (pin "D2") (pinfunction "PE4_D2") (pintype "bidirectional"))
    )
    (net (code "185") (name "unconnected-(U7D-PE5-PadD1)") (class "Default")
      (node (ref "U7") (pin "D1") (pinfunction "PE5_D1") (pintype "bidirectional"))
    )
    (net (code "186") (name "unconnected-(U7D-PH1-OSC_OUT-PadJ1)") (class "Default")
      (node (ref "U7") (pin "J1") (pinfunction "PH1-OSC_OUT_J1") (pintype "bidirectional"))
    )
    (net (code "187") (name "unconnected-(U7E-PI8-PadE4)") (class "Default")
      (node (ref "U7") (pin "E4") (pinfunction "PI8_E4") (pintype "bidirectional"))
    )
    (net (code "188") (name "unconnected-(U7E-PK3-PadC8)") (class "Default")
      (node (ref "U7") (pin "C8") (pinfunction "PK3_C8") (pintype "bidirectional"))
    )
    (net (code "189") (name "unconnected-(U7E-PK4-PadB8)") (class "Default")
      (node (ref "U7") (pin "B8") (pinfunction "PK4_B8") (pintype "bidirectional"))
    )
  )
)
